# GOLpHAT_rev1.net
KiCad netlist of a schematic drawn in EAGLE
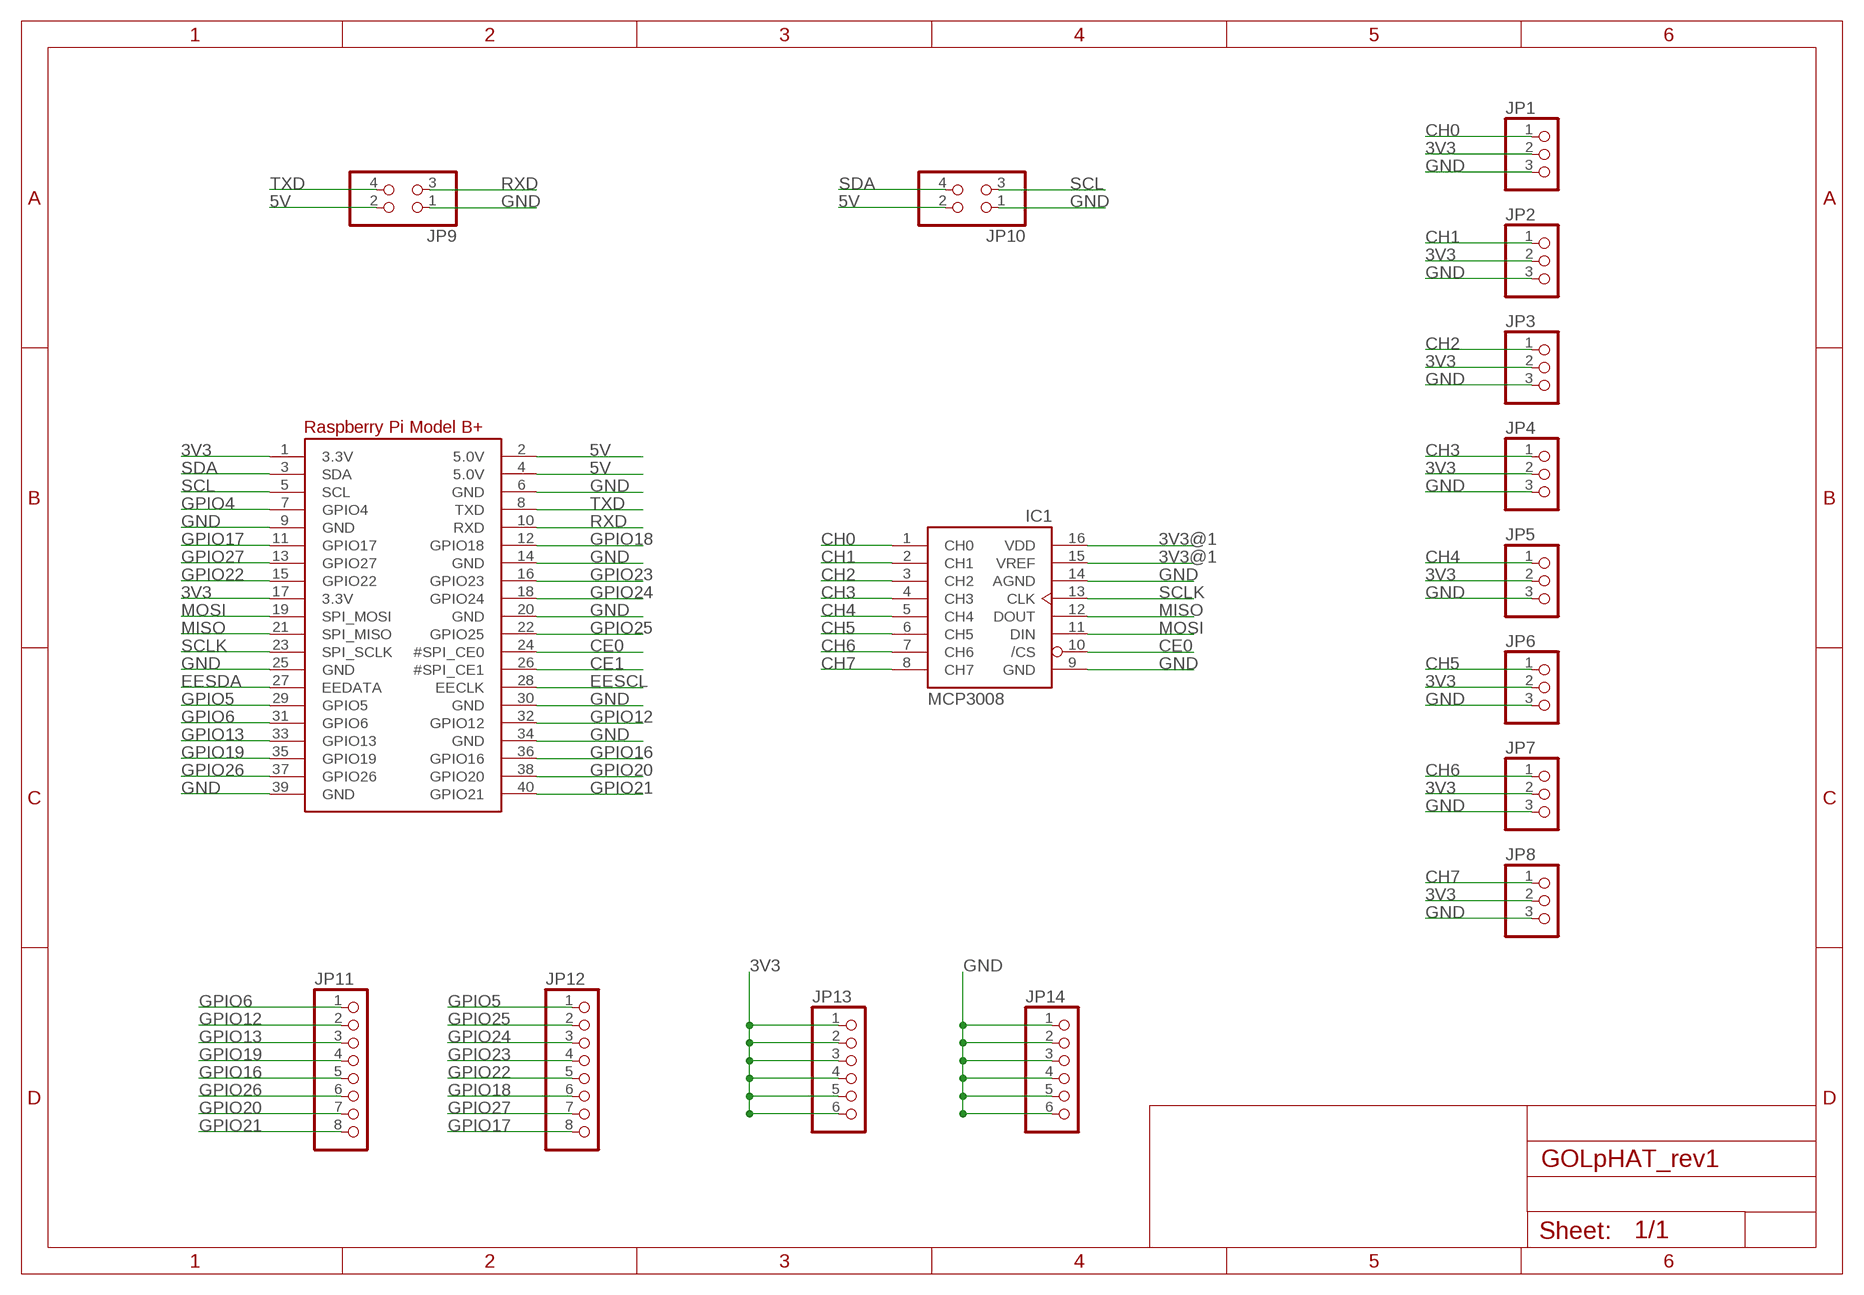
[diagram p0: schematic, sheet 1]

(export (version "E")
  (design (tool "Eeschema 10.0.6"))
  (components
    (comp (ref "IC1")
      (value "MCP3008")
      (footprint "eagle-import:DIL16")
      (libsource (lib "eagle-import") (part "MCP3008"))
    )
    (comp (ref "JP1")
      (value "PINHD-1X3")
      (footprint "eagle-import:1X03")
      (libsource (lib "eagle-import") (part "PINHD-1X3"))
    )
    (comp (ref "JP2")
      (value "PINHD-1X3")
      (footprint "eagle-import:1X03")
      (libsource (lib "eagle-import") (part "PINHD-1X3"))
    )
    (comp (ref "JP3")
      (value "PINHD-1X3")
      (footprint "eagle-import:1X03")
      (libsource (lib "eagle-import") (part "PINHD-1X3"))
    )
    (comp (ref "JP4")
      (value "PINHD-1X3")
      (footprint "eagle-import:1X03")
      (libsource (lib "eagle-import") (part "PINHD-1X3"))
    )
    (comp (ref "JP5")
      (value "PINHD-1X3")
      (footprint "eagle-import:1X03")
      (libsource (lib "eagle-import") (part "PINHD-1X3"))
    )
    (comp (ref "JP6")
      (value "PINHD-1X3")
      (footprint "eagle-import:1X03")
      (libsource (lib "eagle-import") (part "PINHD-1X3"))
    )
    (comp (ref "JP7")
      (value "PINHD-1X3")
      (footprint "eagle-import:1X03")
      (libsource (lib "eagle-import") (part "PINHD-1X3"))
    )
    (comp (ref "JP8")
      (value "PINHD-1X3")
      (footprint "eagle-import:1X03")
      (libsource (lib "eagle-import") (part "PINHD-1X3"))
    )
    (comp (ref "JP9")
      (value "PINHD-2X2")
      (footprint "eagle-import:2X02")
      (libsource (lib "eagle-import") (part "PINHD-2X2"))
    )
    (comp (ref "JP10")
      (value "PINHD-2X2")
      (footprint "eagle-import:2X02")
      (libsource (lib "eagle-import") (part "PINHD-2X2"))
    )
    (comp (ref "JP11")
      (value "PINHD-1X8CLEANBIG")
      (footprint "eagle-import:1X08-CLEANBIG")
      (libsource (lib "eagle-import") (part "PINHD-1X8CLEANBIG"))
    )
    (comp (ref "JP12")
      (value "PINHD-1X8CLEANBIG")
      (footprint "eagle-import:1X08-CLEANBIG")
      (libsource (lib "eagle-import") (part "PINHD-1X8CLEANBIG"))
    )
    (comp (ref "JP13")
      (value "PINHD-1X6CB")
      (footprint "eagle-import:1X06-CLEANBIG")
      (libsource (lib "eagle-import") (part "PINHD-1X6CB"))
    )
    (comp (ref "JP14")
      (value "PINHD-1X6CB")
      (footprint "eagle-import:1X06-CLEANBIG")
      (libsource (lib "eagle-import") (part "PINHD-1X6CB"))
    )
    (comp (ref "RPI1")
      (value "RASPBERRYPI_BPLUS_PHAT")
      (footprint "eagle-import:PI_BONNET")
      (libsource (lib "eagle-import") (part "RASPBERRYPI_BPLUS_PHAT"))
    )
  )
  (nets
    (net (code "1") (name "/3V3") (class "Default")
      (node (ref "JP1") (pin "2") (pinfunction "2_2") (pintype "passive"))
      (node (ref "JP13") (pin "1") (pinfunction "1_1") (pintype "passive"))
      (node (ref "JP13") (pin "2") (pinfunction "2_2") (pintype "passive"))
      (node (ref "JP13") (pin "3") (pinfunction "3_3") (pintype "passive"))
      (node (ref "JP13") (pin "4") (pinfunction "4_4") (pintype "passive"))
      (node (ref "JP13") (pin "5") (pinfunction "5_5") (pintype "passive"))
      (node (ref "JP13") (pin "6") (pinfunction "6_6") (pintype "passive"))
      (node (ref "JP2") (pin "2") (pinfunction "2_2") (pintype "passive"))
      (node (ref "JP3") (pin "2") (pinfunction "2_2") (pintype "passive"))
      (node (ref "JP4") (pin "2") (pinfunction "2_2") (pintype "passive"))
      (node (ref "JP5") (pin "2") (pinfunction "2_2") (pintype "passive"))
      (node (ref "JP6") (pin "2") (pinfunction "2_2") (pintype "passive"))
      (node (ref "JP7") (pin "2") (pinfunction "2_2") (pintype "passive"))
      (node (ref "JP8") (pin "2") (pinfunction "2_2") (pintype "passive"))
      (node (ref "RPI1") (pin "1") (pinfunction "3.3V_1") (pintype "power_in"))
      (node (ref "RPI1") (pin "17") (pinfunction "3.3V_17") (pintype "power_in"))
    )
    (net (code "2") (name "/3V3@1") (class "Default")
      (node (ref "IC1") (pin "15") (pinfunction "VREF_15") (pintype "input"))
      (node (ref "IC1") (pin "16") (pinfunction "VDD_16") (pintype "power_in"))
    )
    (net (code "3") (name "/5V") (class "Default")
      (node (ref "JP10") (pin "2") (pinfunction "2_2") (pintype "passive"))
      (node (ref "JP9") (pin "2") (pinfunction "2_2") (pintype "passive"))
      (node (ref "RPI1") (pin "2") (pinfunction "5.0V_2") (pintype "power_in"))
      (node (ref "RPI1") (pin "4") (pinfunction "5.0V_4") (pintype "power_in"))
    )
    (net (code "4") (name "/CE0") (class "Default")
      (node (ref "IC1") (pin "10") (pinfunction "/CS_10") (pintype "input"))
      (node (ref "RPI1") (pin "24") (pinfunction "#SPI_CE0_24") (pintype "bidirectional"))
    )
    (net (code "5") (name "/CE1") (class "Default")
      (node (ref "RPI1") (pin "26") (pinfunction "#SPI_CE1_26") (pintype "bidirectional"))
    )
    (net (code "6") (name "/CH0") (class "Default")
      (node (ref "IC1") (pin "1") (pinfunction "CH0_1") (pintype "input"))
      (node (ref "JP1") (pin "1") (pinfunction "1_1") (pintype "passive"))
    )
    (net (code "7") (name "/CH1") (class "Default")
      (node (ref "IC1") (pin "2") (pinfunction "CH1_2") (pintype "input"))
      (node (ref "JP2") (pin "1") (pinfunction "1_1") (pintype "passive"))
    )
    (net (code "8") (name "/CH2") (class "Default")
      (node (ref "IC1") (pin "3") (pinfunction "CH2_3") (pintype "input"))
      (node (ref "JP3") (pin "1") (pinfunction "1_1") (pintype "passive"))
    )
    (net (code "9") (name "/CH3") (class "Default")
      (node (ref "IC1") (pin "4") (pinfunction "CH3_4") (pintype "input"))
      (node (ref "JP4") (pin "1") (pinfunction "1_1") (pintype "passive"))
    )
    (net (code "10") (name "/CH4") (class "Default")
      (node (ref "IC1") (pin "5") (pinfunction "CH4_5") (pintype "input"))
      (node (ref "JP5") (pin "1") (pinfunction "1_1") (pintype "passive"))
    )
    (net (code "11") (name "/CH5") (class "Default")
      (node (ref "IC1") (pin "6") (pinfunction "CH5_6") (pintype "input"))
      (node (ref "JP6") (pin "1") (pinfunction "1_1") (pintype "passive"))
    )
    (net (code "12") (name "/CH6") (class "Default")
      (node (ref "IC1") (pin "7") (pinfunction "CH6_7") (pintype "input"))
      (node (ref "JP7") (pin "1") (pinfunction "1_1") (pintype "passive"))
    )
    (net (code "13") (name "/CH7") (class "Default")
      (node (ref "IC1") (pin "8") (pinfunction "CH7_8") (pintype "input"))
      (node (ref "JP8") (pin "1") (pinfunction "1_1") (pintype "passive"))
    )
    (net (code "14") (name "/EESCL") (class "Default")
      (node (ref "RPI1") (pin "28") (pinfunction "EECLK_28") (pintype "bidirectional"))
    )
    (net (code "15") (name "/EESDA") (class "Default")
      (node (ref "RPI1") (pin "27") (pinfunction "EEDATA_27") (pintype "bidirectional"))
    )
    (net (code "16") (name "/GND") (class "Default")
      (node (ref "IC1") (pin "14") (pinfunction "AGND_14") (pintype "power_in"))
      (node (ref "IC1") (pin "9") (pinfunction "GND_9") (pintype "power_in"))
      (node (ref "JP1") (pin "3") (pinfunction "3_3") (pintype "passive"))
      (node (ref "JP10") (pin "1") (pinfunction "1_1") (pintype "passive"))
      (node (ref "JP14") (pin "1") (pinfunction "1_1") (pintype "passive"))
      (node (ref "JP14") (pin "2") (pinfunction "2_2") (pintype "passive"))
      (node (ref "JP14") (pin "3") (pinfunction "3_3") (pintype "passive"))
      (node (ref "JP14") (pin "4") (pinfunction "4_4") (pintype "passive"))
      (node (ref "JP14") (pin "5") (pinfunction "5_5") (pintype "passive"))
      (node (ref "JP14") (pin "6") (pinfunction "6_6") (pintype "passive"))
      (node (ref "JP2") (pin "3") (pinfunction "3_3") (pintype "passive"))
      (node (ref "JP3") (pin "3") (pinfunction "3_3") (pintype "passive"))
      (node (ref "JP4") (pin "3") (pinfunction "3_3") (pintype "passive"))
      (node (ref "JP5") (pin "3") (pinfunction "3_3") (pintype "passive"))
      (node (ref "JP6") (pin "3") (pinfunction "3_3") (pintype "passive"))
      (node (ref "JP7") (pin "3") (pinfunction "3_3") (pintype "passive"))
      (node (ref "JP8") (pin "3") (pinfunction "3_3") (pintype "passive"))
      (node (ref "JP9") (pin "1") (pinfunction "1_1") (pintype "passive"))
      (node (ref "RPI1") (pin "14") (pinfunction "GND_14") (pintype "power_in"))
      (node (ref "RPI1") (pin "20") (pinfunction "GND_20") (pintype "power_in"))
      (node (ref "RPI1") (pin "25") (pinfunction "GND_25") (pintype "power_in"))
      (node (ref "RPI1") (pin "30") (pinfunction "GND_30") (pintype "power_in"))
      (node (ref "RPI1") (pin "34") (pinfunction "GND_34") (pintype "power_in"))
      (node (ref "RPI1") (pin "39") (pinfunction "GND_39") (pintype "power_in"))
      (node (ref "RPI1") (pin "6") (pinfunction "GND_6") (pintype "power_in"))
      (node (ref "RPI1") (pin "9") (pinfunction "GND_9") (pintype "power_in"))
    )
    (net (code "17") (name "/GPIO4") (class "Default")
      (node (ref "RPI1") (pin "7") (pinfunction "GPIO4_7") (pintype "bidirectional"))
    )
    (net (code "18") (name "/GPIO5") (class "Default")
      (node (ref "JP12") (pin "1") (pinfunction "1_1") (pintype "passive"))
      (node (ref "RPI1") (pin "29") (pinfunction "GPIO5_29") (pintype "bidirectional"))
    )
    (net (code "19") (name "/GPIO6") (class "Default")
      (node (ref "JP11") (pin "1") (pinfunction "1_1") (pintype "passive"))
      (node (ref "RPI1") (pin "31") (pinfunction "GPIO6_31") (pintype "bidirectional"))
    )
    (net (code "20") (name "/GPIO12") (class "Default")
      (node (ref "JP11") (pin "2") (pinfunction "2_2") (pintype "passive"))
      (node (ref "RPI1") (pin "32") (pinfunction "GPIO12_32") (pintype "bidirectional"))
    )
    (net (code "21") (name "/GPIO13") (class "Default")
      (node (ref "JP11") (pin "3") (pinfunction "3_3") (pintype "passive"))
      (node (ref "RPI1") (pin "33") (pinfunction "GPIO13_33") (pintype "bidirectional"))
    )
    (net (code "22") (name "/GPIO16") (class "Default")
      (node (ref "JP11") (pin "5") (pinfunction "5_5") (pintype "passive"))
      (node (ref "RPI1") (pin "36") (pinfunction "GPIO16_36") (pintype "bidirectional"))
    )
    (net (code "23") (name "/GPIO17") (class "Default")
      (node (ref "JP12") (pin "8") (pinfunction "8_8") (pintype "passive"))
      (node (ref "RPI1") (pin "11") (pinfunction "GPIO17_11") (pintype "bidirectional"))
    )
    (net (code "24") (name "/GPIO18") (class "Default")
      (node (ref "JP12") (pin "6") (pinfunction "6_6") (pintype "passive"))
      (node (ref "RPI1") (pin "12") (pinfunction "GPIO18_12") (pintype "bidirectional"))
    )
    (net (code "25") (name "/GPIO19") (class "Default")
      (node (ref "JP11") (pin "4") (pinfunction "4_4") (pintype "passive"))
      (node (ref "RPI1") (pin "35") (pinfunction "GPIO19_35") (pintype "bidirectional"))
    )
    (net (code "26") (name "/GPIO20") (class "Default")
      (node (ref "JP11") (pin "7") (pinfunction "7_7") (pintype "passive"))
      (node (ref "RPI1") (pin "38") (pinfunction "GPIO20_38") (pintype "bidirectional"))
    )
    (net (code "27") (name "/GPIO21") (class "Default")
      (node (ref "JP11") (pin "8") (pinfunction "8_8") (pintype "passive"))
      (node (ref "RPI1") (pin "40") (pinfunction "GPIO21_40") (pintype "bidirectional"))
    )
    (net (code "28") (name "/GPIO22") (class "Default")
      (node (ref "JP12") (pin "5") (pinfunction "5_5") (pintype "passive"))
      (node (ref "RPI1") (pin "15") (pinfunction "GPIO22_15") (pintype "bidirectional"))
    )
    (net (code "29") (name "/GPIO23") (class "Default")
      (node (ref "JP12") (pin "4") (pinfunction "4_4") (pintype "passive"))
      (node (ref "RPI1") (pin "16") (pinfunction "GPIO23_16") (pintype "bidirectional"))
    )
    (net (code "30") (name "/GPIO24") (class "Default")
      (node (ref "JP12") (pin "3") (pinfunction "3_3") (pintype "passive"))
      (node (ref "RPI1") (pin "18") (pinfunction "GPIO24_18") (pintype "bidirectional"))
    )
    (net (code "31") (name "/GPIO25") (class "Default")
      (node (ref "JP12") (pin "2") (pinfunction "2_2") (pintype "passive"))
      (node (ref "RPI1") (pin "22") (pinfunction "GPIO25_22") (pintype "bidirectional"))
    )
    (net (code "32") (name "/GPIO26") (class "Default")
      (node (ref "JP11") (pin "6") (pinfunction "6_6") (pintype "passive"))
      (node (ref "RPI1") (pin "37") (pinfunction "GPIO26_37") (pintype "bidirectional"))
    )
    (net (code "33") (name "/GPIO27") (class "Default")
      (node (ref "JP12") (pin "7") (pinfunction "7_7") (pintype "passive"))
      (node (ref "RPI1") (pin "13") (pinfunction "GPIO27_13") (pintype "bidirectional"))
    )
    (net (code "34") (name "/MISO") (class "Default")
      (node (ref "IC1") (pin "12") (pinfunction "DOUT_12") (pintype "output"))
      (node (ref "RPI1") (pin "21") (pinfunction "SPI_MISO_21") (pintype "bidirectional"))
    )
    (net (code "35") (name "/MOSI") (class "Default")
      (node (ref "IC1") (pin "11") (pinfunction "DIN_11") (pintype "input"))
      (node (ref "RPI1") (pin "19") (pinfunction "SPI_MOSI_19") (pintype "bidirectional"))
    )
    (net (code "36") (name "/RXD") (class "Default")
      (node (ref "JP9") (pin "3") (pinfunction "3_3") (pintype "passive"))
      (node (ref "RPI1") (pin "10") (pinfunction "RXD_10") (pintype "bidirectional"))
    )
    (net (code "37") (name "/SCL") (class "Default")
      (node (ref "JP10") (pin "3") (pinfunction "3_3") (pintype "passive"))
      (node (ref "RPI1") (pin "5") (pinfunction "SCL_5") (pintype "bidirectional"))
    )
    (net (code "38") (name "/SCLK") (class "Default")
      (node (ref "IC1") (pin "13") (pinfunction "CLK_13") (pintype "input"))
      (node (ref "RPI1") (pin "23") (pinfunction "SPI_SCLK_23") (pintype "bidirectional"))
    )
    (net (code "39") (name "/SDA") (class "Default")
      (node (ref "JP10") (pin "4") (pinfunction "4_4") (pintype "passive"))
      (node (ref "RPI1") (pin "3") (pinfunction "SDA_3") (pintype "bidirectional"))
    )
    (net (code "40") (name "/TXD") (class "Default")
      (node (ref "JP9") (pin "4") (pinfunction "4_4") (pintype "passive"))
      (node (ref "RPI1") (pin "8") (pinfunction "TXD_8") (pintype "bidirectional"))
    )
  )
)
